# 21_GPIOs_EXP.net
KiCad netlist of a schematic drawn in Altium Designer
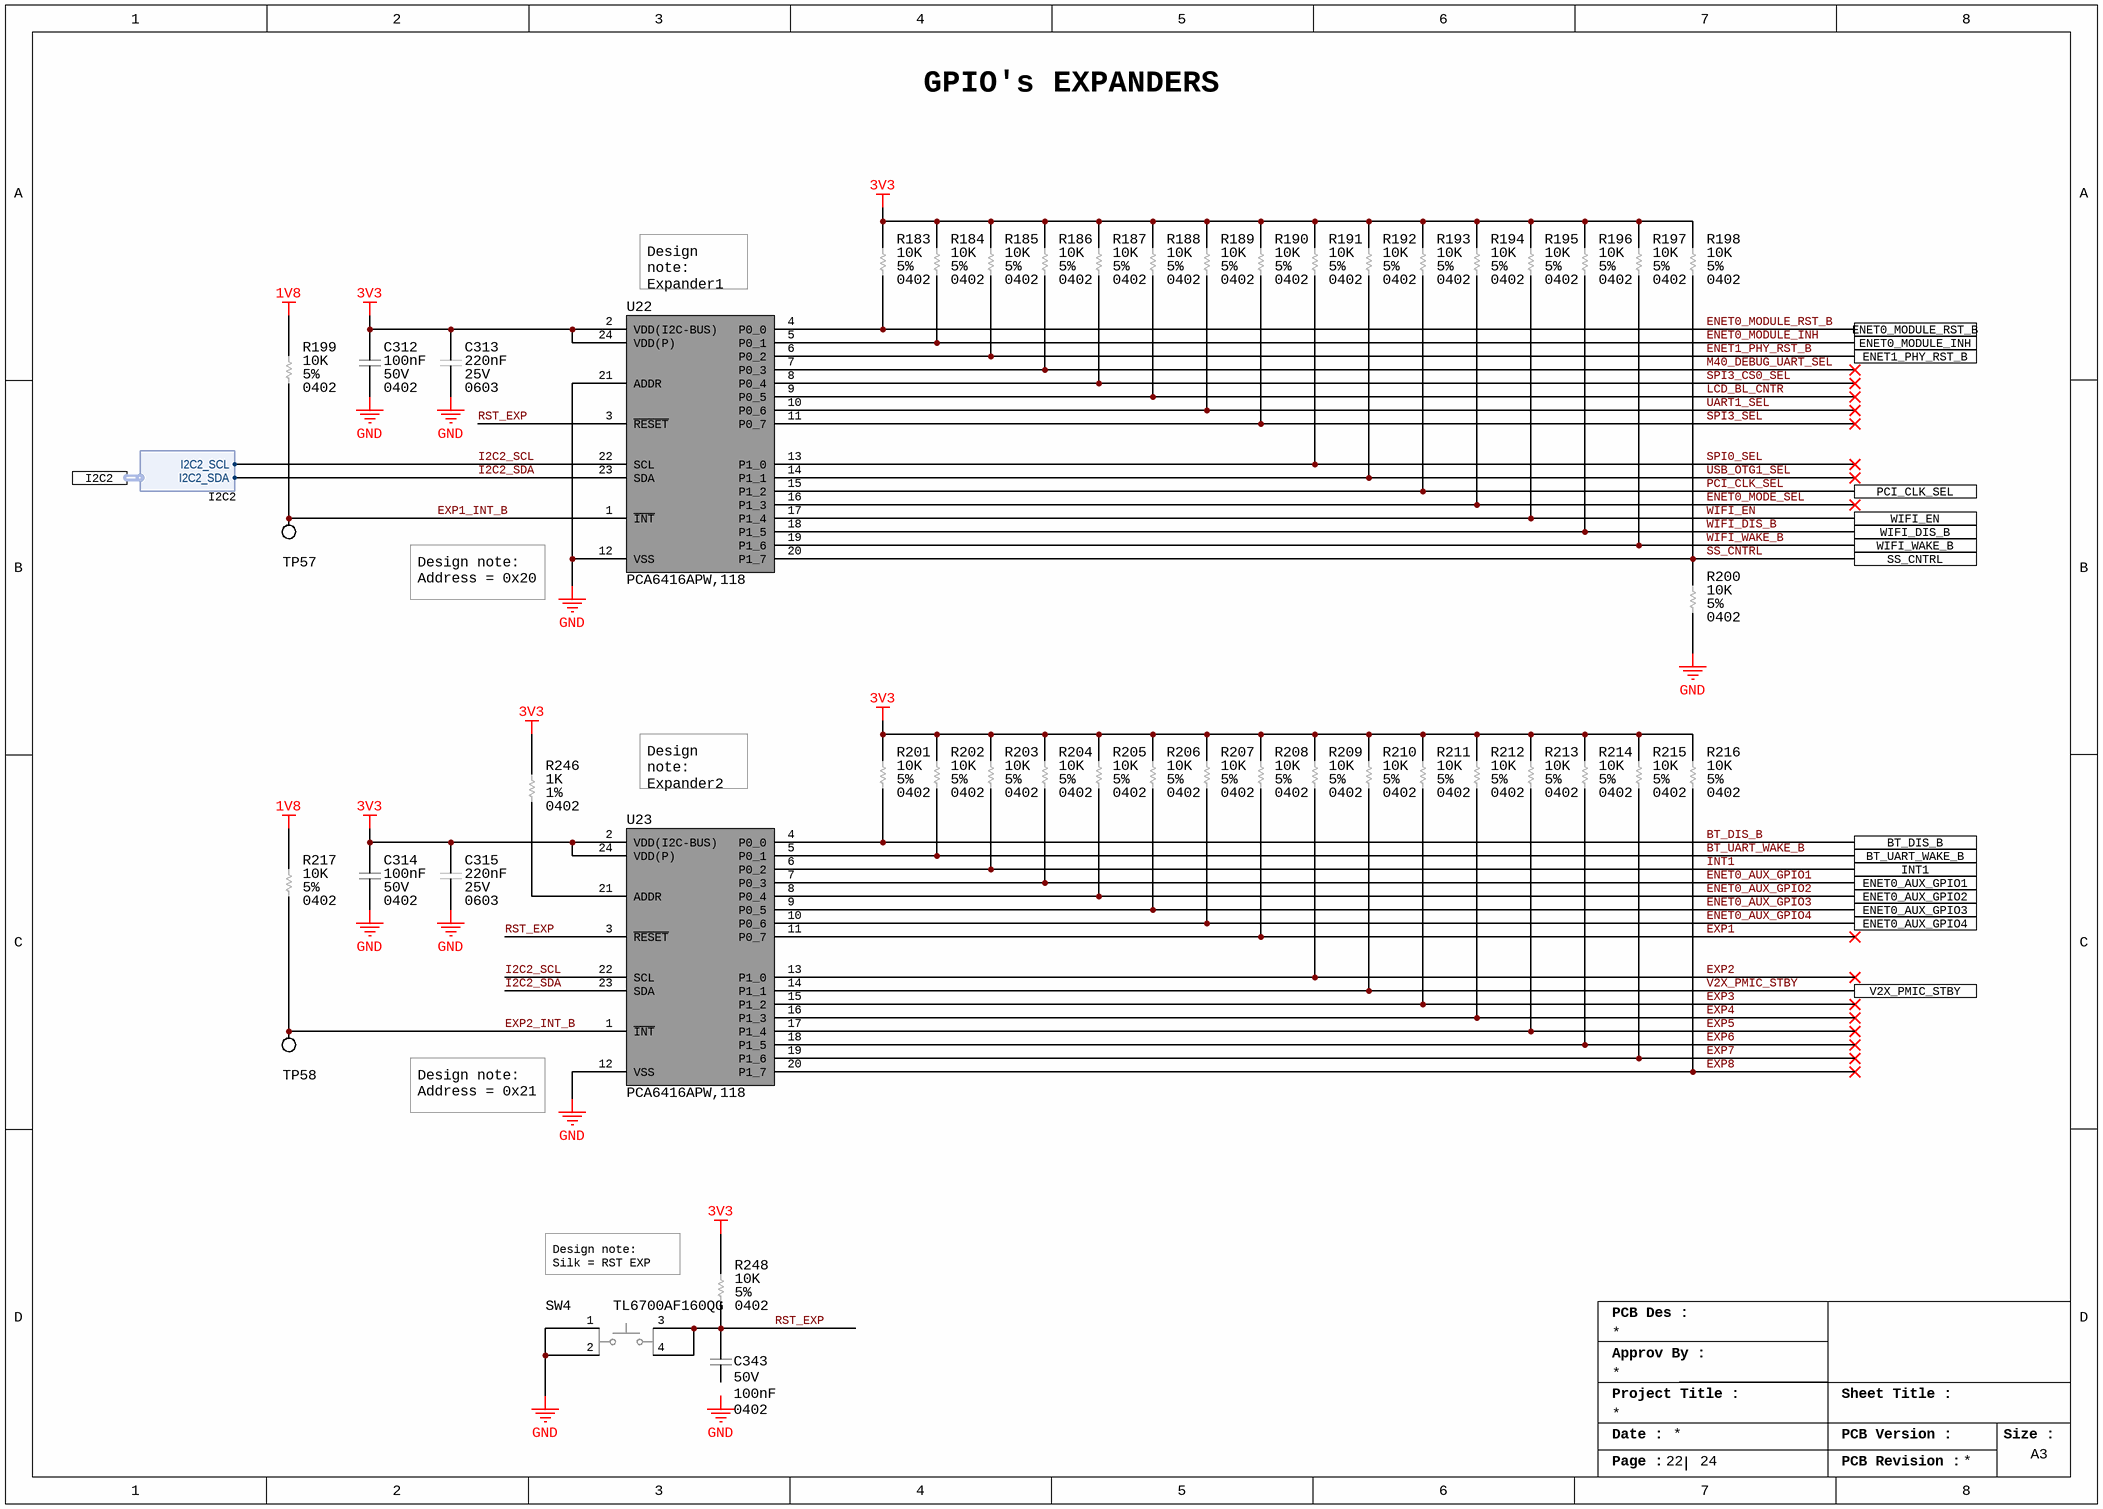
[diagram p0: 21_GPIOs_EXP.SchDoc]

(export (version "E")
  (design (tool "Eeschema 10.0.6"))
  (components
    (comp (ref "C312")
      (value "GRM155R71H104KE14D")
      (footprint "CAP_0402_CAPC1005X05N")
      (description "Multilayer Ceramic Capacitor, 0.1 uF, 16 V, ± 10%, X7R, 0402 [1005 Metric]")
      (fields
        (field (name "MANUFACTURER") "Murata")
        (field (name "TOLERANCE") "10%")
        (field (name "VOLTAGE RATING") "50V")
        (field (name "CAPACITANCE") "100nF")
        (field (name "CASE/PACKAGE") "0402")
      )
      (libsource (lib "Electronic Devices_LIB") (part "CAP_100NF_50V_X7R_0402"))
    )
    (comp (ref "C313")
      (value "GRM188R71E224KA88D")
      (footprint "CAP_0603_CAPC1608X08N")
      (description "Multilayer Ceramic Capacitor, 0.22 uF, 25 V, ± 10%, X7R, 0603 [1608 Metric]")
      (fields
        (field (name "MANUFACTURER") "Murata")
        (field (name "TOLERANCE") "10%")
        (field (name "CASE/PACKAGE") "0603")
        (field (name "VOLTAGE RATING") "25V")
        (field (name "CAPACITANCE") "220nF")
      )
      (libsource (lib "Electronic Devices_LIB") (part "CAP_0.22uF_25V_X7R_0603"))
    )
    (comp (ref "C314")
      (value "GRM155R71H104KE14D")
      (footprint "CAP_0402_CAPC1005X05N")
      (description "Multilayer Ceramic Capacitor, 0.1 uF, 16 V, ± 10%, X7R, 0402 [1005 Metric]")
      (fields
        (field (name "MANUFACTURER") "Murata")
        (field (name "TOLERANCE") "10%")
        (field (name "VOLTAGE RATING") "50V")
        (field (name "CAPACITANCE") "100nF")
        (field (name "CASE/PACKAGE") "0402")
      )
      (libsource (lib "Electronic Devices_LIB") (part "CAP_100NF_50V_X7R_0402"))
    )
    (comp (ref "C315")
      (value "GRM188R71E224KA88D")
      (footprint "CAP_0603_CAPC1608X08N")
      (description "Multilayer Ceramic Capacitor, 0.22 uF, 25 V, ± 10%, X7R, 0603 [1608 Metric]")
      (fields
        (field (name "MANUFACTURER") "Murata")
        (field (name "TOLERANCE") "10%")
        (field (name "CASE/PACKAGE") "0603")
        (field (name "VOLTAGE RATING") "25V")
        (field (name "CAPACITANCE") "220nF")
      )
      (libsource (lib "Electronic Devices_LIB") (part "CAP_0.22uF_25V_X7R_0603"))
    )
    (comp (ref "C343")
      (value "GRM155R71H104KE14D")
      (footprint "CAP_0402_CAPC1005X05N")
      (description "Multilayer Ceramic Capacitor, 0.1 uF, 16 V, ± 10%, X7R, 0402 [1005 Metric]")
      (fields
        (field (name "MANUFACTURER") "Murata")
        (field (name "TOLERANCE") "10%")
        (field (name "VOLTAGE RATING") "50V")
        (field (name "CAPACITANCE") "100nF")
        (field (name "CASE/PACKAGE") "0402")
      )
      (libsource (lib "Electronic Devices_LIB") (part "CAP_100NF_50V_X7R_0402"))
    )
    (comp (ref "R183")
      (value "ERJ-2GEJ103X")
      (footprint "RES_0402_RESC1005X04N")
      (description "Res Thick Film 0402 10K Ohm 5% 1/10W ±200ppm/°C Molded SMD Punched Carrier T/R")
      (fields
        (field (name "MANUFACTURER") "Panasonic")
        (field (name "TOLERANCE") "5%")
        (field (name "RESISTANCE") "10K")
        (field (name "CASE/PACKAGE") "0402")
      )
      (libsource (lib "Electronic Devices_LIB") (part "RES_10K_5%_100mW_0402"))
    )
    (comp (ref "R184")
      (value "ERJ-2GEJ103X")
      (footprint "RES_0402_RESC1005X04N")
      (description "Res Thick Film 0402 10K Ohm 5% 1/10W ±200ppm/°C Molded SMD Punched Carrier T/R")
      (fields
        (field (name "MANUFACTURER") "Panasonic")
        (field (name "TOLERANCE") "5%")
        (field (name "RESISTANCE") "10K")
        (field (name "CASE/PACKAGE") "0402")
      )
      (libsource (lib "Electronic Devices_LIB") (part "RES_10K_5%_100mW_0402"))
    )
    (comp (ref "R185")
      (value "ERJ-2GEJ103X")
      (footprint "RES_0402_RESC1005X04N")
      (description "Res Thick Film 0402 10K Ohm 5% 1/10W ±200ppm/°C Molded SMD Punched Carrier T/R")
      (fields
        (field (name "MANUFACTURER") "Panasonic")
        (field (name "TOLERANCE") "5%")
        (field (name "RESISTANCE") "10K")
        (field (name "CASE/PACKAGE") "0402")
      )
      (libsource (lib "Electronic Devices_LIB") (part "RES_10K_5%_100mW_0402"))
    )
    (comp (ref "R186")
      (value "ERJ-2GEJ103X")
      (footprint "RES_0402_RESC1005X04N")
      (description "Res Thick Film 0402 10K Ohm 5% 1/10W ±200ppm/°C Molded SMD Punched Carrier T/R")
      (fields
        (field (name "MANUFACTURER") "Panasonic")
        (field (name "TOLERANCE") "5%")
        (field (name "RESISTANCE") "10K")
        (field (name "CASE/PACKAGE") "0402")
      )
      (libsource (lib "Electronic Devices_LIB") (part "RES_10K_5%_100mW_0402"))
    )
    (comp (ref "R187")
      (value "ERJ-2GEJ103X")
      (footprint "RES_0402_RESC1005X04N")
      (description "Res Thick Film 0402 10K Ohm 5% 1/10W ±200ppm/°C Molded SMD Punched Carrier T/R")
      (fields
        (field (name "MANUFACTURER") "Panasonic")
        (field (name "TOLERANCE") "5%")
        (field (name "RESISTANCE") "10K")
        (field (name "CASE/PACKAGE") "0402")
      )
      (libsource (lib "Electronic Devices_LIB") (part "RES_10K_5%_100mW_0402"))
    )
    (comp (ref "R188")
      (value "ERJ-2GEJ103X")
      (footprint "RES_0402_RESC1005X04N")
      (description "Res Thick Film 0402 10K Ohm 5% 1/10W ±200ppm/°C Molded SMD Punched Carrier T/R")
      (fields
        (field (name "MANUFACTURER") "Panasonic")
        (field (name "TOLERANCE") "5%")
        (field (name "RESISTANCE") "10K")
        (field (name "CASE/PACKAGE") "0402")
      )
      (libsource (lib "Electronic Devices_LIB") (part "RES_10K_5%_100mW_0402"))
    )
    (comp (ref "R189")
      (value "ERJ-2GEJ103X")
      (footprint "RES_0402_RESC1005X04N")
      (description "Res Thick Film 0402 10K Ohm 5% 1/10W ±200ppm/°C Molded SMD Punched Carrier T/R")
      (fields
        (field (name "MANUFACTURER") "Panasonic")
        (field (name "TOLERANCE") "5%")
        (field (name "RESISTANCE") "10K")
        (field (name "CASE/PACKAGE") "0402")
      )
      (libsource (lib "Electronic Devices_LIB") (part "RES_10K_5%_100mW_0402"))
    )
    (comp (ref "R190")
      (value "ERJ-2GEJ103X")
      (footprint "RES_0402_RESC1005X04N")
      (description "Res Thick Film 0402 10K Ohm 5% 1/10W ±200ppm/°C Molded SMD Punched Carrier T/R")
      (fields
        (field (name "MANUFACTURER") "Panasonic")
        (field (name "TOLERANCE") "5%")
        (field (name "RESISTANCE") "10K")
        (field (name "CASE/PACKAGE") "0402")
      )
      (libsource (lib "Electronic Devices_LIB") (part "RES_10K_5%_100mW_0402"))
    )
    (comp (ref "R191")
      (value "ERJ-2GEJ103X")
      (footprint "RES_0402_RESC1005X04N")
      (description "Res Thick Film 0402 10K Ohm 5% 1/10W ±200ppm/°C Molded SMD Punched Carrier T/R")
      (fields
        (field (name "MANUFACTURER") "Panasonic")
        (field (name "TOLERANCE") "5%")
        (field (name "RESISTANCE") "10K")
        (field (name "CASE/PACKAGE") "0402")
      )
      (libsource (lib "Electronic Devices_LIB") (part "RES_10K_5%_100mW_0402"))
    )
    (comp (ref "R192")
      (value "ERJ-2GEJ103X")
      (footprint "RES_0402_RESC1005X04N")
      (description "Res Thick Film 0402 10K Ohm 5% 1/10W ±200ppm/°C Molded SMD Punched Carrier T/R")
      (fields
        (field (name "MANUFACTURER") "Panasonic")
        (field (name "TOLERANCE") "5%")
        (field (name "RESISTANCE") "10K")
        (field (name "CASE/PACKAGE") "0402")
      )
      (libsource (lib "Electronic Devices_LIB") (part "RES_10K_5%_100mW_0402"))
    )
    (comp (ref "R193")
      (value "ERJ-2GEJ103X")
      (footprint "RES_0402_RESC1005X04N")
      (description "Res Thick Film 0402 10K Ohm 5% 1/10W ±200ppm/°C Molded SMD Punched Carrier T/R")
      (fields
        (field (name "MANUFACTURER") "Panasonic")
        (field (name "TOLERANCE") "5%")
        (field (name "RESISTANCE") "10K")
        (field (name "CASE/PACKAGE") "0402")
      )
      (libsource (lib "Electronic Devices_LIB") (part "RES_10K_5%_100mW_0402"))
    )
    (comp (ref "R194")
      (value "ERJ-2GEJ103X")
      (footprint "RES_0402_RESC1005X04N")
      (description "Res Thick Film 0402 10K Ohm 5% 1/10W ±200ppm/°C Molded SMD Punched Carrier T/R")
      (fields
        (field (name "MANUFACTURER") "Panasonic")
        (field (name "TOLERANCE") "5%")
        (field (name "RESISTANCE") "10K")
        (field (name "CASE/PACKAGE") "0402")
      )
      (libsource (lib "Electronic Devices_LIB") (part "RES_10K_5%_100mW_0402"))
    )
    (comp (ref "R195")
      (value "ERJ-2GEJ103X")
      (footprint "RES_0402_RESC1005X04N")
      (description "Res Thick Film 0402 10K Ohm 5% 1/10W ±200ppm/°C Molded SMD Punched Carrier T/R")
      (fields
        (field (name "MANUFACTURER") "Panasonic")
        (field (name "TOLERANCE") "5%")
        (field (name "RESISTANCE") "10K")
        (field (name "CASE/PACKAGE") "0402")
      )
      (libsource (lib "Electronic Devices_LIB") (part "RES_10K_5%_100mW_0402"))
    )
    (comp (ref "R196")
      (value "ERJ-2GEJ103X")
      (footprint "RES_0402_RESC1005X04N")
      (description "Res Thick Film 0402 10K Ohm 5% 1/10W ±200ppm/°C Molded SMD Punched Carrier T/R")
      (fields
        (field (name "MANUFACTURER") "Panasonic")
        (field (name "TOLERANCE") "5%")
        (field (name "RESISTANCE") "10K")
        (field (name "CASE/PACKAGE") "0402")
      )
      (libsource (lib "Electronic Devices_LIB") (part "RES_10K_5%_100mW_0402"))
    )
    (comp (ref "R197")
      (value "ERJ-2GEJ103X")
      (footprint "RES_0402_RESC1005X04N")
      (description "Res Thick Film 0402 10K Ohm 5% 1/10W ±200ppm/°C Molded SMD Punched Carrier T/R")
      (fields
        (field (name "MANUFACTURER") "Panasonic")
        (field (name "TOLERANCE") "5%")
        (field (name "RESISTANCE") "10K")
        (field (name "CASE/PACKAGE") "0402")
      )
      (libsource (lib "Electronic Devices_LIB") (part "RES_10K_5%_100mW_0402"))
    )
    (comp (ref "R198")
      (value "ERJ-2GEJ103X")
      (footprint "RES_0402_RESC1005X04N")
      (description "Res Thick Film 0402 10K Ohm 5% 1/10W ±200ppm/°C Molded SMD Punched Carrier T/R")
      (fields
        (field (name "MANUFACTURER") "Panasonic")
        (field (name "TOLERANCE") "5%")
        (field (name "RESISTANCE") "10K")
        (field (name "CASE/PACKAGE") "0402")
      )
      (libsource (lib "Electronic Devices_LIB") (part "RES_10K_5%_100mW_0402"))
    )
    (comp (ref "R199")
      (value "ERJ-2GEJ103X")
      (footprint "RES_0402_RESC1005X04N")
      (description "Res Thick Film 0402 10K Ohm 5% 1/10W ±200ppm/°C Molded SMD Punched Carrier T/R")
      (fields
        (field (name "MANUFACTURER") "Panasonic")
        (field (name "TOLERANCE") "5%")
        (field (name "RESISTANCE") "10K")
        (field (name "CASE/PACKAGE") "0402")
      )
      (libsource (lib "Electronic Devices_LIB") (part "RES_10K_5%_100mW_0402"))
    )
    (comp (ref "R200")
      (value "ERJ-2GEJ103X")
      (footprint "RES_0402_RESC1005X04N")
      (description "Res Thick Film 0402 10K Ohm 5% 1/10W ±200ppm/°C Molded SMD Punched Carrier T/R")
      (fields
        (field (name "MANUFACTURER") "Panasonic")
        (field (name "TOLERANCE") "5%")
        (field (name "RESISTANCE") "10K")
        (field (name "CASE/PACKAGE") "0402")
      )
      (libsource (lib "Electronic Devices_LIB") (part "RES_10K_5%_100mW_0402"))
    )
    (comp (ref "R201")
      (value "ERJ-2GEJ103X")
      (footprint "RES_0402_RESC1005X04N")
      (description "Res Thick Film 0402 10K Ohm 5% 1/10W ±200ppm/°C Molded SMD Punched Carrier T/R")
      (fields
        (field (name "MANUFACTURER") "Panasonic")
        (field (name "TOLERANCE") "5%")
        (field (name "RESISTANCE") "10K")
        (field (name "CASE/PACKAGE") "0402")
      )
      (libsource (lib "Electronic Devices_LIB") (part "RES_10K_5%_100mW_0402"))
    )
    (comp (ref "R202")
      (value "ERJ-2GEJ103X")
      (footprint "RES_0402_RESC1005X04N")
      (description "Res Thick Film 0402 10K Ohm 5% 1/10W ±200ppm/°C Molded SMD Punched Carrier T/R")
      (fields
        (field (name "MANUFACTURER") "Panasonic")
        (field (name "TOLERANCE") "5%")
        (field (name "RESISTANCE") "10K")
        (field (name "CASE/PACKAGE") "0402")
      )
      (libsource (lib "Electronic Devices_LIB") (part "RES_10K_5%_100mW_0402"))
    )
    (comp (ref "R203")
      (value "ERJ-2GEJ103X")
      (footprint "RES_0402_RESC1005X04N")
      (description "Res Thick Film 0402 10K Ohm 5% 1/10W ±200ppm/°C Molded SMD Punched Carrier T/R")
      (fields
        (field (name "MANUFACTURER") "Panasonic")
        (field (name "TOLERANCE") "5%")
        (field (name "RESISTANCE") "10K")
        (field (name "CASE/PACKAGE") "0402")
      )
      (libsource (lib "Electronic Devices_LIB") (part "RES_10K_5%_100mW_0402"))
    )
    (comp (ref "R204")
      (value "ERJ-2GEJ103X")
      (footprint "RES_0402_RESC1005X04N")
      (description "Res Thick Film 0402 10K Ohm 5% 1/10W ±200ppm/°C Molded SMD Punched Carrier T/R")
      (fields
        (field (name "MANUFACTURER") "Panasonic")
        (field (name "TOLERANCE") "5%")
        (field (name "RESISTANCE") "10K")
        (field (name "CASE/PACKAGE") "0402")
      )
      (libsource (lib "Electronic Devices_LIB") (part "RES_10K_5%_100mW_0402"))
    )
    (comp (ref "R205")
      (value "ERJ-2GEJ103X")
      (footprint "RES_0402_RESC1005X04N")
      (description "Res Thick Film 0402 10K Ohm 5% 1/10W ±200ppm/°C Molded SMD Punched Carrier T/R")
      (fields
        (field (name "MANUFACTURER") "Panasonic")
        (field (name "TOLERANCE") "5%")
        (field (name "RESISTANCE") "10K")
        (field (name "CASE/PACKAGE") "0402")
      )
      (libsource (lib "Electronic Devices_LIB") (part "RES_10K_5%_100mW_0402"))
    )
    (comp (ref "R206")
      (value "ERJ-2GEJ103X")
      (footprint "RES_0402_RESC1005X04N")
      (description "Res Thick Film 0402 10K Ohm 5% 1/10W ±200ppm/°C Molded SMD Punched Carrier T/R")
      (fields
        (field (name "MANUFACTURER") "Panasonic")
        (field (name "TOLERANCE") "5%")
        (field (name "RESISTANCE") "10K")
        (field (name "CASE/PACKAGE") "0402")
      )
      (libsource (lib "Electronic Devices_LIB") (part "RES_10K_5%_100mW_0402"))
    )
    (comp (ref "R207")
      (value "ERJ-2GEJ103X")
      (footprint "RES_0402_RESC1005X04N")
      (description "Res Thick Film 0402 10K Ohm 5% 1/10W ±200ppm/°C Molded SMD Punched Carrier T/R")
      (fields
        (field (name "MANUFACTURER") "Panasonic")
        (field (name "TOLERANCE") "5%")
        (field (name "RESISTANCE") "10K")
        (field (name "CASE/PACKAGE") "0402")
      )
      (libsource (lib "Electronic Devices_LIB") (part "RES_10K_5%_100mW_0402"))
    )
    (comp (ref "R208")
      (value "ERJ-2GEJ103X")
      (footprint "RES_0402_RESC1005X04N")
      (description "Res Thick Film 0402 10K Ohm 5% 1/10W ±200ppm/°C Molded SMD Punched Carrier T/R")
      (fields
        (field (name "MANUFACTURER") "Panasonic")
        (field (name "TOLERANCE") "5%")
        (field (name "RESISTANCE") "10K")
        (field (name "CASE/PACKAGE") "0402")
      )
      (libsource (lib "Electronic Devices_LIB") (part "RES_10K_5%_100mW_0402"))
    )
    (comp (ref "R209")
      (value "ERJ-2GEJ103X")
      (footprint "RES_0402_RESC1005X04N")
      (description "Res Thick Film 0402 10K Ohm 5% 1/10W ±200ppm/°C Molded SMD Punched Carrier T/R")
      (fields
        (field (name "MANUFACTURER") "Panasonic")
        (field (name "TOLERANCE") "5%")
        (field (name "RESISTANCE") "10K")
        (field (name "CASE/PACKAGE") "0402")
      )
      (libsource (lib "Electronic Devices_LIB") (part "RES_10K_5%_100mW_0402"))
    )
    (comp (ref "R210")
      (value "ERJ-2GEJ103X")
      (footprint "RES_0402_RESC1005X04N")
      (description "Res Thick Film 0402 10K Ohm 5% 1/10W ±200ppm/°C Molded SMD Punched Carrier T/R")
      (fields
        (field (name "MANUFACTURER") "Panasonic")
        (field (name "TOLERANCE") "5%")
        (field (name "RESISTANCE") "10K")
        (field (name "CASE/PACKAGE") "0402")
      )
      (libsource (lib "Electronic Devices_LIB") (part "RES_10K_5%_100mW_0402"))
    )
    (comp (ref "R211")
      (value "ERJ-2GEJ103X")
      (footprint "RES_0402_RESC1005X04N")
      (description "Res Thick Film 0402 10K Ohm 5% 1/10W ±200ppm/°C Molded SMD Punched Carrier T/R")
      (fields
        (field (name "MANUFACTURER") "Panasonic")
        (field (name "TOLERANCE") "5%")
        (field (name "RESISTANCE") "10K")
        (field (name "CASE/PACKAGE") "0402")
      )
      (libsource (lib "Electronic Devices_LIB") (part "RES_10K_5%_100mW_0402"))
    )
    (comp (ref "R212")
      (value "ERJ-2GEJ103X")
      (footprint "RES_0402_RESC1005X04N")
      (description "Res Thick Film 0402 10K Ohm 5% 1/10W ±200ppm/°C Molded SMD Punched Carrier T/R")
      (fields
        (field (name "MANUFACTURER") "Panasonic")
        (field (name "TOLERANCE") "5%")
        (field (name "RESISTANCE") "10K")
        (field (name "CASE/PACKAGE") "0402")
      )
      (libsource (lib "Electronic Devices_LIB") (part "RES_10K_5%_100mW_0402"))
    )
    (comp (ref "R213")
      (value "ERJ-2GEJ103X")
      (footprint "RES_0402_RESC1005X04N")
      (description "Res Thick Film 0402 10K Ohm 5% 1/10W ±200ppm/°C Molded SMD Punched Carrier T/R")
      (fields
        (field (name "MANUFACTURER") "Panasonic")
        (field (name "TOLERANCE") "5%")
        (field (name "RESISTANCE") "10K")
        (field (name "CASE/PACKAGE") "0402")
      )
      (libsource (lib "Electronic Devices_LIB") (part "RES_10K_5%_100mW_0402"))
    )
    (comp (ref "R214")
      (value "ERJ-2GEJ103X")
      (footprint "RES_0402_RESC1005X04N")
      (description "Res Thick Film 0402 10K Ohm 5% 1/10W ±200ppm/°C Molded SMD Punched Carrier T/R")
      (fields
        (field (name "MANUFACTURER") "Panasonic")
        (field (name "TOLERANCE") "5%")
        (field (name "RESISTANCE") "10K")
        (field (name "CASE/PACKAGE") "0402")
      )
      (libsource (lib "Electronic Devices_LIB") (part "RES_10K_5%_100mW_0402"))
    )
    (comp (ref "R215")
      (value "ERJ-2GEJ103X")
      (footprint "RES_0402_RESC1005X04N")
      (description "Res Thick Film 0402 10K Ohm 5% 1/10W ±200ppm/°C Molded SMD Punched Carrier T/R")
      (fields
        (field (name "MANUFACTURER") "Panasonic")
        (field (name "TOLERANCE") "5%")
        (field (name "RESISTANCE") "10K")
        (field (name "CASE/PACKAGE") "0402")
      )
      (libsource (lib "Electronic Devices_LIB") (part "RES_10K_5%_100mW_0402"))
    )
    (comp (ref "R216")
      (value "ERJ-2GEJ103X")
      (footprint "RES_0402_RESC1005X04N")
      (description "Res Thick Film 0402 10K Ohm 5% 1/10W ±200ppm/°C Molded SMD Punched Carrier T/R")
      (fields
        (field (name "MANUFACTURER") "Panasonic")
        (field (name "TOLERANCE") "5%")
        (field (name "RESISTANCE") "10K")
        (field (name "CASE/PACKAGE") "0402")
      )
      (libsource (lib "Electronic Devices_LIB") (part "RES_10K_5%_100mW_0402"))
    )
    (comp (ref "R217")
      (value "ERJ-2GEJ103X")
      (footprint "RES_0402_RESC1005X04N")
      (description "Res Thick Film 0402 10K Ohm 5% 1/10W ±200ppm/°C Molded SMD Punched Carrier T/R")
      (fields
        (field (name "MANUFACTURER") "Panasonic")
        (field (name "TOLERANCE") "5%")
        (field (name "RESISTANCE") "10K")
        (field (name "CASE/PACKAGE") "0402")
      )
      (libsource (lib "Electronic Devices_LIB") (part "RES_10K_5%_100mW_0402"))
    )
    (comp (ref "R246")
      (value "ERJ-2RKF1001X")
      (footprint "RES_0402_RESC1005X04N")
      (description "RES SMD 1K OHM 1% 1/10W 0402")
      (fields
        (field (name "MANUFACTURER") "Panasonic")
        (field (name "RESISTANCE") "1K")
        (field (name "TOLERANCE") "1%")
        (field (name "CASE/PACKAGE") "0402")
      )
      (libsource (lib "Electronic Devices_LIB") (part "RES_1K_1%_100mW_0402"))
    )
    (comp (ref "R248")
      (value "ERJ-2GEJ103X")
      (footprint "RES_0402_RESC1005X04N")
      (description "Res Thick Film 0402 10K Ohm 5% 1/10W ±200ppm/°C Molded SMD Punched Carrier T/R")
      (fields
        (field (name "MANUFACTURER") "Panasonic")
        (field (name "TOLERANCE") "5%")
        (field (name "RESISTANCE") "10K")
        (field (name "CASE/PACKAGE") "0402")
      )
      (libsource (lib "Electronic Devices_LIB") (part "RES_10K_5%_100mW_0402"))
    )
    (comp (ref "SW4")
      (value "TL6700AF160QG")
      (footprint "SW_TL6700AF160QG")
      (description "TL6700 Series SPST 1.6 N Round Button Gull Wing SMT Sealed Tactile Switch")
      (fields (field (name "MANUFACTURER") "E-Switch"))
      (libsource (lib "Electronic Devices_LIB") (part "SWITCH_SPST_TL6700AF160QG"))
    )
    (comp (ref "TP57")
      (value "NO COMPONENT")
      (footprint "TP_PAD_0.5MM_SMD_ROUND")
      (description "Test Point, SMD pad, round, 1.5mm, 1.6mm, 3mm diameter")
      (libsource (lib "Electronic Devices_LIB") (part "TP_PAD_SMD_SMALL"))
    )
    (comp (ref "TP58")
      (value "NO COMPONENT")
      (footprint "TP_PAD_0.5MM_SMD_ROUND")
      (description "Test Point, SMD pad, round, 1.5mm, 1.6mm, 3mm diameter")
      (libsource (lib "Electronic Devices_LIB") (part "TP_PAD_SMD_SMALL"))
    )
    (comp (ref "U22")
      (value "PCA6416APW,118")
      (footprint "PCA6416APW118")
      (description "I2C/SMBus Interface 100kHz/400kHz 5.5V 24-Pin TSSOP T/R")
      (fields (field (name "MANUFACTURER") "NXP Semiconductors"))
      (libsource (lib "Electronic Devices_LIB") (part "IC_EXPANDER_16_PCA6416APW,118"))
    )
    (comp (ref "U23")
      (value "PCA6416APW,118")
      (footprint "PCA6416APW118")
      (description "I2C/SMBus Interface 100kHz/400kHz 5.5V 24-Pin TSSOP T/R")
      (fields (field (name "MANUFACTURER") "NXP Semiconductors"))
      (libsource (lib "Electronic Devices_LIB") (part "IC_EXPANDER_16_PCA6416APW,118"))
    )
  )
  (nets
    (net (code "2") (name "/BT_DIS_B") (class "Default")
      (node (ref "R201") (pin "1") (pinfunction "1_1") (pintype "passive"))
      (node (ref "U23") (pin "4") (pinfunction "P0_0_4") (pintype "passive"))
    )
    (net (code "3") (name "/BT_UART_WAKE_B") (class "Default")
      (node (ref "R202") (pin "1") (pinfunction "1_1") (pintype "passive"))
      (node (ref "U23") (pin "5") (pinfunction "P0_1_5") (pintype "passive"))
    )
    (net (code "4") (name "/ENET0_AUX_GPIO1") (class "Default")
      (node (ref "R204") (pin "1") (pinfunction "1_1") (pintype "passive"))
      (node (ref "U23") (pin "7") (pinfunction "P0_3_7") (pintype "passive"))
    )
    (net (code "5") (name "/ENET0_AUX_GPIO2") (class "Default")
      (node (ref "R205") (pin "1") (pinfunction "1_1") (pintype "passive"))
      (node (ref "U23") (pin "8") (pinfunction "P0_4_8") (pintype "passive"))
    )
    (net (code "6") (name "/ENET0_AUX_GPIO3") (class "Default")
      (node (ref "R206") (pin "1") (pinfunction "1_1") (pintype "passive"))
      (node (ref "U23") (pin "9") (pinfunction "P0_5_9") (pintype "passive"))
    )
    (net (code "7") (name "/ENET0_AUX_GPIO4") (class "Default")
      (node (ref "R207") (pin "1") (pinfunction "1_1") (pintype "passive"))
      (node (ref "U23") (pin "10") (pinfunction "P0_6_10") (pintype "passive"))
    )
    (net (code "8") (name "/ENET0_MODE_SEL") (class "Default")
      (node (ref "R194") (pin "1") (pinfunction "1_1") (pintype "passive"))
      (node (ref "U22") (pin "16") (pinfunction "P1_3_16") (pintype "passive"))
    )
    (net (code "9") (name "/ENET0_MODULE_INH") (class "Default")
      (node (ref "R184") (pin "1") (pinfunction "1_1") (pintype "passive"))
      (node (ref "U22") (pin "5") (pinfunction "P0_1_5") (pintype "passive"))
    )
    (net (code "10") (name "/ENET0_MODULE_RST_B") (class "Default")
      (node (ref "R183") (pin "1") (pinfunction "1_1") (pintype "passive"))
      (node (ref "U22") (pin "4") (pinfunction "P0_0_4") (pintype "passive"))
    )
    (net (code "11") (name "/ENET1_PHY_RST_B") (class "Default")
      (node (ref "R185") (pin "1") (pinfunction "1_1") (pintype "passive"))
      (node (ref "U22") (pin "6") (pinfunction "P0_2_6") (pintype "passive"))
    )
    (net (code "12") (name "/EXP1") (class "Default")
      (node (ref "R208") (pin "1") (pinfunction "1_1") (pintype "passive"))
      (node (ref "U23") (pin "11") (pinfunction "P0_7_11") (pintype "passive"))
    )
    (net (code "13") (name "/EXP1_INT_B") (class "Default")
      (node (ref "R199") (pin "1") (pinfunction "1_1") (pintype "passive"))
      (node (ref "TP57") (pin "1") (pinfunction "1_1") (pintype "passive"))
      (node (ref "U22") (pin "1") (pinfunction "~{INT}_1") (pintype "passive"))
    )
    (net (code "14") (name "/EXP2") (class "Default")
      (node (ref "R209") (pin "1") (pinfunction "1_1") (pintype "passive"))
      (node (ref "U23") (pin "13") (pinfunction "P1_0_13") (pintype "passive"))
    )
    (net (code "15") (name "/EXP2_INT_B") (class "Default")
      (node (ref "R217") (pin "1") (pinfunction "1_1") (pintype "passive"))
      (node (ref "TP58") (pin "1") (pinfunction "1_1") (pintype "passive"))
      (node (ref "U23") (pin "1") (pinfunction "~{INT}_1") (pintype "passive"))
    )
    (net (code "16") (name "/EXP3") (class "Default")
      (node (ref "R211") (pin "1") (pinfunction "1_1") (pintype "passive"))
      (node (ref "U23") (pin "15") (pinfunction "P1_2_15") (pintype "passive"))
    )
    (net (code "17") (name "/EXP4") (class "Default")
      (node (ref "R212") (pin "1") (pinfunction "1_1") (pintype "passive"))
      (node (ref "U23") (pin "16") (pinfunction "P1_3_16") (pintype "passive"))
    )
    (net (code "18") (name "/EXP5") (class "Default")
      (node (ref "R213") (pin "1") (pinfunction "1_1") (pintype "passive"))
      (node (ref "U23") (pin "17") (pinfunction "P1_4_17") (pintype "passive"))
    )
    (net (code "19") (name "/EXP6") (class "Default")
      (node (ref "R214") (pin "1") (pinfunction "1_1") (pintype "passive"))
      (node (ref "U23") (pin "18") (pinfunction "P1_5_18") (pintype "passive"))
    )
    (net (code "20") (name "/EXP7") (class "Default")
      (node (ref "R215") (pin "1") (pinfunction "1_1") (pintype "passive"))
      (node (ref "U23") (pin "19") (pinfunction "P1_6_19") (pintype "passive"))
    )
    (net (code "21") (name "/EXP8") (class "Default")
      (node (ref "R216") (pin "1") (pinfunction "1_1") (pintype "passive"))
      (node (ref "U23") (pin "20") (pinfunction "P1_7_20") (pintype "passive"))
    )
    (net (code "22") (name "/I2C2_SCL") (class "Default")
      (node (ref "U22") (pin "22") (pinfunction "SCL_22") (pintype "passive"))
      (node (ref "U23") (pin "22") (pinfunction "SCL_22") (pintype "passive"))
    )
    (net (code "23") (name "/I2C2_SDA") (class "Default")
      (node (ref "U22") (pin "23") (pinfunction "SDA_23") (pintype "passive"))
      (node (ref "U23") (pin "23") (pinfunction "SDA_23") (pintype "passive"))
    )
    (net (code "24") (name "/INT1") (class "Default")
      (node (ref "R203") (pin "1") (pinfunction "1_1") (pintype "passive"))
      (node (ref "U23") (pin "6") (pinfunction "P0_2_6") (pintype "passive"))
    )
    (net (code "25") (name "/LCD_BL_CNTR") (class "Default")
      (node (ref "R188") (pin "1") (pinfunction "1_1") (pintype "passive"))
      (node (ref "U22") (pin "9") (pinfunction "P0_5_9") (pintype "passive"))
    )
    (net (code "26") (name "/M40_DEBUG_UART_SEL") (class "Default")
      (node (ref "R186") (pin "1") (pinfunction "1_1") (pintype "passive"))
      (node (ref "U22") (pin "7") (pinfunction "P0_3_7") (pintype "passive"))
    )
    (net (code "27") (name "/PCI_CLK_SEL") (class "Default")
      (node (ref "R193") (pin "1") (pinfunction "1_1") (pintype "passive"))
      (node (ref "U22") (pin "15") (pinfunction "P1_2_15") (pintype "passive"))
    )
    (net (code "28") (name "/RST_EXP") (class "Default")
      (node (ref "C343") (pin "2") (pinfunction "2_2") (pintype "passive"))
      (node (ref "R248") (pin "2") (pinfunction "2_2") (pintype "passive"))
      (node (ref "SW4") (pin "3") (pinfunction "3_3") (pintype "passive"))
      (node (ref "SW4") (pin "4") (pinfunction "4_4") (pintype "passive"))
      (node (ref "U22") (pin "3") (pinfunction "~{RESET}_3") (pintype "passive"))
      (node (ref "U23") (pin "3") (pinfunction "~{RESET}_3") (pintype "passive"))
    )
    (net (code "29") (name "/SPI0_SEL") (class "Default")
      (node (ref "R191") (pin "1") (pinfunction "1_1") (pintype "passive"))
      (node (ref "U22") (pin "13") (pinfunction "P1_0_13") (pintype "passive"))
    )
    (net (code "30") (name "/SPI3_CS0_SEL") (class "Default")
      (node (ref "R187") (pin "1") (pinfunction "1_1") (pintype "passive"))
      (node (ref "U22") (pin "8") (pinfunction "P0_4_8") (pintype "passive"))
    )
    (net (code "31") (name "/SPI3_SEL") (class "Default")
      (node (ref "R190") (pin "1") (pinfunction "1_1") (pintype "passive"))
      (node (ref "U22") (pin "11") (pinfunction "P0_7_11") (pintype "passive"))
    )
    (net (code "32") (name "/SS_CNTRL") (class "Default")
      (node (ref "R198") (pin "1") (pinfunction "1_1") (pintype "passive"))
      (node (ref "R200") (pin "2") (pinfunction "2_2") (pintype "passive"))
      (node (ref "U22") (pin "20") (pinfunction "P1_7_20") (pintype "passive"))
    )
    (net (code "33") (name "/UART1_SEL") (class "Default")
      (node (ref "R189") (pin "1") (pinfunction "1_1") (pintype "passive"))
      (node (ref "U22") (pin "10") (pinfunction "P0_6_10") (pintype "passive"))
    )
    (net (code "34") (name "/USB_OTG1_SEL") (class "Default")
      (node (ref "R192") (pin "1") (pinfunction "1_1") (pintype "passive"))
      (node (ref "U22") (pin "14") (pinfunction "P1_1_14") (pintype "passive"))
    )
    (net (code "35") (name "/V2X_PMIC_STBY") (class "Default")
      (node (ref "R210") (pin "1") (pinfunction "1_1") (pintype "passive"))
      (node (ref "U23") (pin "14") (pinfunction "P1_1_14") (pintype "passive"))
    )
    (net (code "36") (name "/WIFI_DIS_B") (class "Default")
      (node (ref "R196") (pin "1") (pinfunction "1_1") (pintype "passive"))
      (node (ref "U22") (pin "18") (pinfunction "P1_5_18") (pintype "passive"))
    )
    (net (code "37") (name "/WIFI_EN") (class "Default")
      (node (ref "R195") (pin "1") (pinfunction "1_1") (pintype "passive"))
      (node (ref "U22") (pin "17") (pinfunction "P1_4_17") (pintype "passive"))
    )
    (net (code "38") (name "/WIFI_WAKE_B") (class "Default")
      (node (ref "R197") (pin "1") (pinfunction "1_1") (pintype "passive"))
      (node (ref "U22") (pin "19") (pinfunction "P1_6_19") (pintype "passive"))
    )
    (net (code "40") (name "1V8") (class "Default")
      (node (ref "R199") (pin "2") (pinfunction "2_2") (pintype "passive"))
      (node (ref "R217") (pin "2") (pinfunction "2_2") (pintype "passive"))
    )
    (net (code "41") (name "3V3") (class "Default")
      (node (ref "C312") (pin "2") (pinfunction "2_2") (pintype "passive"))
      (node (ref "C313") (pin "2") (pinfunction "2_2") (pintype "passive"))
      (node (ref "C314") (pin "2") (pinfunction "2_2") (pintype "passive"))
      (node (ref "C315") (pin "2") (pinfunction "2_2") (pintype "passive"))
      (node (ref "R183") (pin "2") (pinfunction "2_2") (pintype "passive"))
      (node (ref "R184") (pin "2") (pinfunction "2_2") (pintype "passive"))
      (node (ref "R185") (pin "2") (pinfunction "2_2") (pintype "passive"))
      (node (ref "R186") (pin "2") (pinfunction "2_2") (pintype "passive"))
      (node (ref "R187") (pin "2") (pinfunction "2_2") (pintype "passive"))
      (node (ref "R188") (pin "2") (pinfunction "2_2") (pintype "passive"))
      (node (ref "R189") (pin "2") (pinfunction "2_2") (pintype "passive"))
      (node (ref "R190") (pin "2") (pinfunction "2_2") (pintype "passive"))
      (node (ref "R191") (pin "2") (pinfunction "2_2") (pintype "passive"))
      (node (ref "R192") (pin "2") (pinfunction "2_2") (pintype "passive"))
      (node (ref "R193") (pin "2") (pinfunction "2_2") (pintype "passive"))
      (node (ref "R194") (pin "2") (pinfunction "2_2") (pintype "passive"))
      (node (ref "R195") (pin "2") (pinfunction "2_2") (pintype "passive"))
      (node (ref "R196") (pin "2") (pinfunction "2_2") (pintype "passive"))
      (node (ref "R197") (pin "2") (pinfunction "2_2") (pintype "passive"))
      (node (ref "R198") (pin "2") (pinfunction "2_2") (pintype "passive"))
      (node (ref "R201") (pin "2") (pinfunction "2_2") (pintype "passive"))
      (node (ref "R202") (pin "2") (pinfunction "2_2") (pintype "passive"))
      (node (ref "R203") (pin "2") (pinfunction "2_2") (pintype "passive"))
      (node (ref "R204") (pin "2") (pinfunction "2_2") (pintype "passive"))
      (node (ref "R205") (pin "2") (pinfunction "2_2") (pintype "passive"))
      (node (ref "R206") (pin "2") (pinfunction "2_2") (pintype "passive"))
      (node (ref "R207") (pin "2") (pinfunction "2_2") (pintype "passive"))
      (node (ref "R208") (pin "2") (pinfunction "2_2") (pintype "passive"))
      (node (ref "R209") (pin "2") (pinfunction "2_2") (pintype "passive"))
      (node (ref "R210") (pin "2") (pinfunction "2_2") (pintype "passive"))
      (node (ref "R211") (pin "2") (pinfunction "2_2") (pintype "passive"))
      (node (ref "R212") (pin "2") (pinfunction "2_2") (pintype "passive"))
      (node (ref "R213") (pin "2") (pinfunction "2_2") (pintype "passive"))
      (node (ref "R214") (pin "2") (pinfunction "2_2") (pintype "passive"))
      (node (ref "R215") (pin "2") (pinfunction "2_2") (pintype "passive"))
      (node (ref "R216") (pin "2") (pinfunction "2_2") (pintype "passive"))
      (node (ref "R246") (pin "2") (pinfunction "2_2") (pintype "passive"))
      (node (ref "R248") (pin "1") (pinfunction "1_1") (pintype "passive"))
      (node (ref "U22") (pin "2") (pinfunction "VDD(I2C-BUS)_2") (pintype "passive"))
      (node (ref "U22") (pin "24") (pinfunction "VDD(P)_24") (pintype "passive"))
      (node (ref "U23") (pin "2") (pinfunction "VDD(I2C-BUS)_2") (pintype "passive"))
      (node (ref "U23") (pin "24") (pinfunction "VDD(P)_24") (pintype "passive"))
    )
    (net (code "42") (name "GND") (class "Default")
      (node (ref "C312") (pin "1") (pinfunction "1_1") (pintype "passive"))
      (node (ref "C313") (pin "1") (pinfunction "1_1") (pintype "passive"))
      (node (ref "C314") (pin "1") (pinfunction "1_1") (pintype "passive"))
      (node (ref "C315") (pin "1") (pinfunction "1_1") (pintype "passive"))
      (node (ref "R200") (pin "1") (pinfunction "1_1") (pintype "passive"))
      (node (ref "SW4") (pin "1") (pinfunction "1_1") (pintype "passive"))
      (node (ref "SW4") (pin "2") (pinfunction "2_2") (pintype "passive"))
      (node (ref "U22") (pin "12") (pinfunction "VSS_12") (pintype "passive"))
      (node (ref "U22") (pin "21") (pinfunction "ADDR_21") (pintype "passive"))
      (node (ref "U23") (pin "12") (pinfunction "VSS_12") (pintype "passive"))
    )
    (net (code "43") (name "Net-(U23-ADDR)") (class "Default")
      (node (ref "R246") (pin "1") (pinfunction "1_1") (pintype "passive"))
      (node (ref "U23") (pin "21") (pinfunction "ADDR_21") (pintype "passive"))
    )
    (net (code "44") (name "unconnected-(C343-Pad1)") (class "Default")
      (node (ref "C343") (pin "1") (pinfunction "1_1") (pintype "passive"))
    )
  )
)
